# HighPower.net
KiCad netlist of a schematic drawn in Altium Designer
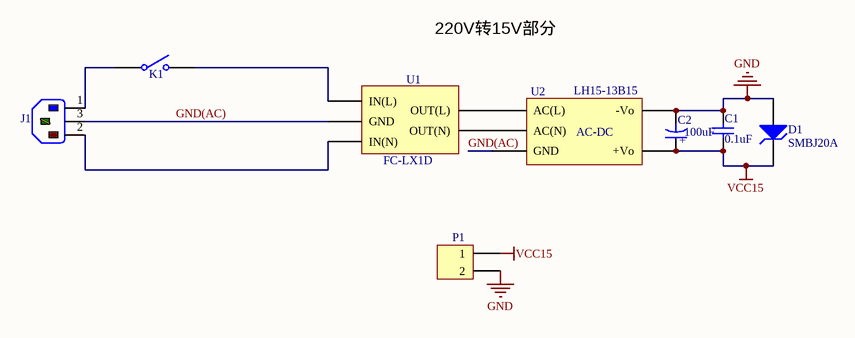
[diagram p0: HighPower.SchDoc]

(export (version "E")
  (design (tool "Eeschema 10.0.6"))
  (components
    (comp (ref "C1")
      (value "0.1uF")
      (footprint "0805")
      (fields (field (name "Comment") "Capacitor-0805"))
      (libsource (lib "原理图库") (part "Capacitor-0805"))
    )
    (comp (ref "C2")
      (value "100uF")
      (footprint "贴片铝电容-8*10.3")
      (fields (field (name "ALTIUM_UNNAMED_1") "+") (field (name "Comment") "电解电容"))
      (libsource (lib "原理图库") (part "电解电容"))
    )
    (comp (ref "D1")
      (value "SMBJ20A")
      (footprint "SMBJ20A")
      (fields (field (name "NAME") "SMBJ20A"))
      (libsource (lib "原理图库") (part "SMBJ20A"))
    )
    (comp (ref "J1") (value "三脚航空插头") (footprint "三脚航空插头") (libsource (lib "原理图库") (part "三脚航空插头")))
    (comp (ref "K1") (value "开关") (footprint "T型接头") (libsource (lib "原理图库") (part "开关")))
    (comp (ref "P1") (value "端子2") (footprint "MOLEX-2") (libsource (lib "原理图库") (part "端子2")))
    (comp (ref "U1")
      (value "FC-LX1D")
      (footprint "FC-LX1D")
      (fields (field (name "NAME") "FC-LX1D"))
      (libsource (lib "原理图库") (part "FC-LX1D"))
    )
    (comp (ref "U2")
      (value "LH10-10B15")
      (footprint "LH10-10B15")
      (fields (field (name "DESCRIBE") "AC-DC") (field (name "NAME") "LH15-13B15"))
      (libsource (lib "原理图库") (part "LH10-10B15"))
    )
  )
  (nets
    (net (code "1") (name "/GND(AC)") (class "Default")
      (node (ref "J1") (pin "3") (pinfunction "3_3") (pintype "passive"))
      (node (ref "U1") (pin "1") (pinfunction "GND_1") (pintype "passive"))
      (node (ref "U2") (pin "1") (pinfunction "GND_1") (pintype "passive"))
    )
    (net (code "2") (name "GND") (class "Default")
      (node (ref "C1") (pin "2") (pinfunction "2_2") (pintype "passive"))
      (node (ref "C2") (pin "1") (pinfunction "1_1") (pintype "passive"))
      (node (ref "D1") (pin "1") (pinfunction "A_1") (pintype "passive"))
      (node (ref "P1") (pin "2") (pinfunction "2_2") (pintype "passive"))
      (node (ref "U2") (pin "4") (pinfunction "-Vo_4") (pintype "passive"))
    )
    (net (code "3") (name "Net-(K1-COMMON)") (class "Default")
      (node (ref "J1") (pin "1") (pinfunction "1_1") (pintype "passive"))
      (node (ref "K1") (pin "1") (pinfunction "COMMON_1") (pintype "passive"))
    )
    (net (code "4") (name "Net-(K1-NO)") (class "Default")
      (node (ref "K1") (pin "2") (pinfunction "NO_2") (pintype "passive"))
      (node (ref "U1") (pin "3") (pinfunction "IN(L)_3") (pintype "passive"))
    )
    (net (code "5") (name "Net-(U1-IN(N))") (class "Default")
      (node (ref "J1") (pin "2") (pinfunction "2_2") (pintype "passive"))
      (node (ref "U1") (pin "2") (pinfunction "IN(N)_2") (pintype "passive"))
    )
    (net (code "6") (name "Net-(U1-OUT(L))") (class "Default")
      (node (ref "U1") (pin "4") (pinfunction "OUT(L)_4") (pintype "passive"))
      (node (ref "U2") (pin "3") (pinfunction "AC(L)_3") (pintype "passive"))
    )
    (net (code "7") (name "Net-(U1-OUT(N))") (class "Default")
      (node (ref "U1") (pin "5") (pinfunction "OUT(N)_5") (pintype "passive"))
      (node (ref "U2") (pin "2") (pinfunction "AC(N)_2") (pintype "passive"))
    )
    (net (code "8") (name "VCC15") (class "Default")
      (node (ref "C1") (pin "1") (pinfunction "1_1") (pintype "passive"))
      (node (ref "C2") (pin "2") (pinfunction "2_2") (pintype "passive"))
      (node (ref "D1") (pin "2") (pinfunction "K_2") (pintype "passive"))
      (node (ref "P1") (pin "1") (pinfunction "1_1") (pintype "passive"))
      (node (ref "U2") (pin "8") (pinfunction "+Vo_8") (pintype "passive"))
    )
  )
)
